# EDP_new_schematic.net
KiCad netlist of a schematic drawn in Altium Designer
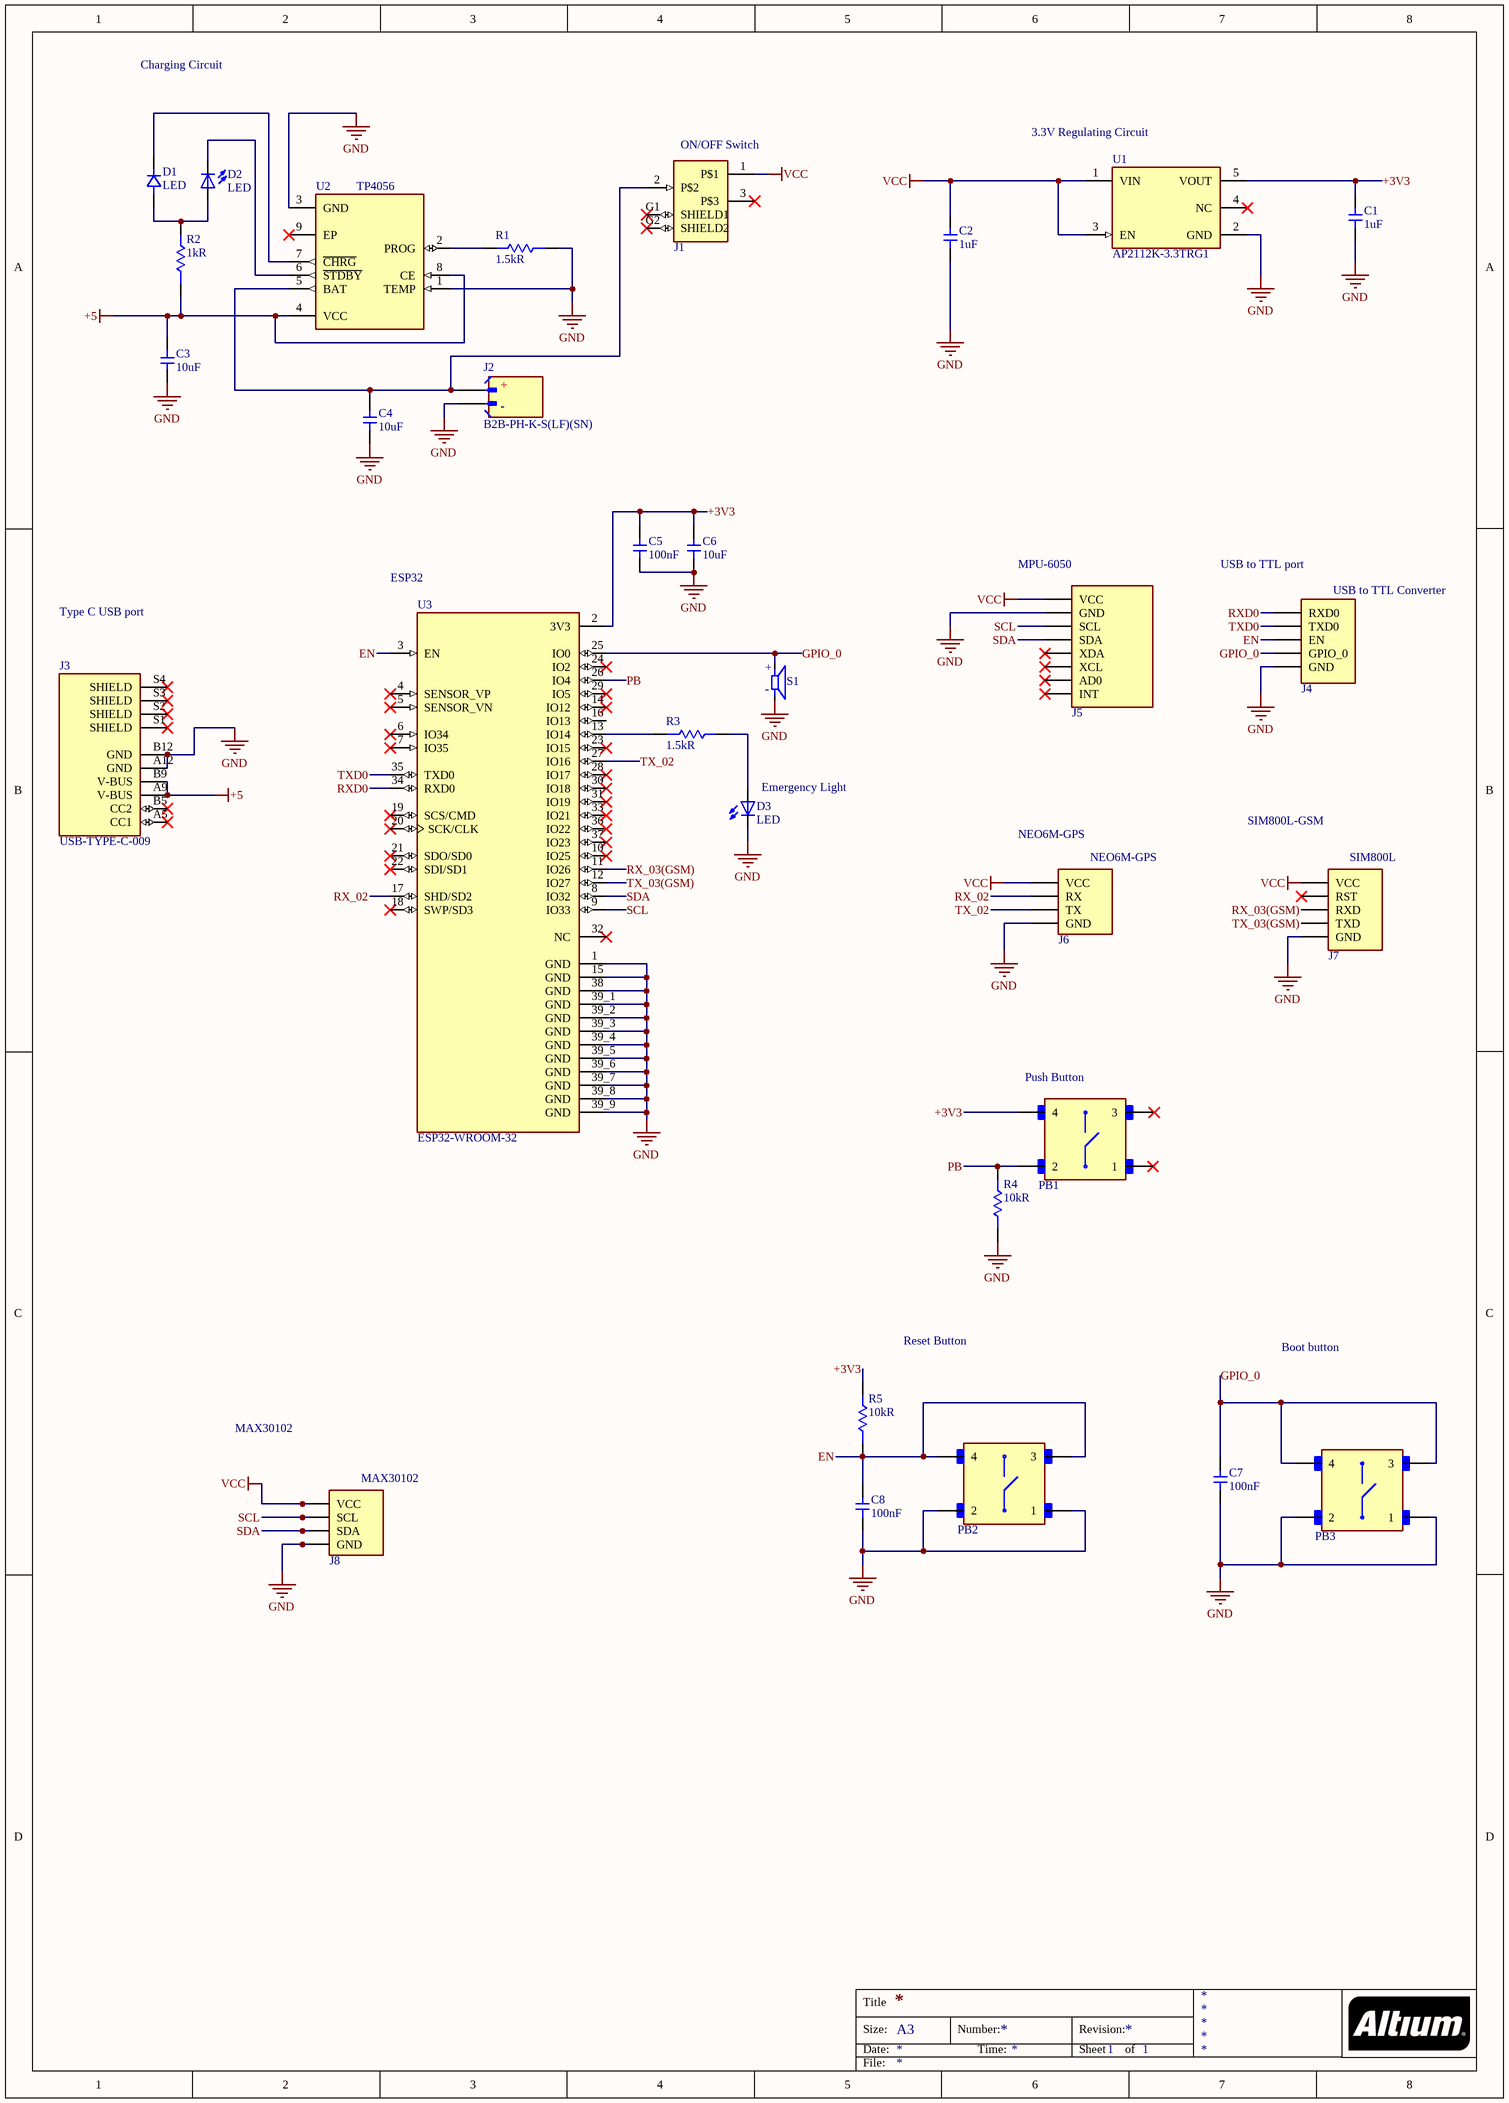
[diagram p0: EDP_new_schematic.SchDoc]

(export (version "E")
  (design (tool "Eeschema 10.0.6"))
  (components
    (comp (ref "C1")
      (value "1uF")
      (footprint "C0805C105K4RACTU")
      (fields
        (field (name "MANUFACTURER") "KEMET")
        (field (name "MANUFACTURER PART NUMBER") "C0805C105K4RACTU")
      )
      (libsource (lib "EDP_integrated_library") (part "C0805C105K4RACTU"))
    )
    (comp (ref "C2")
      (value "1uF")
      (footprint "C0805C105K4RACTU")
      (fields
        (field (name "MANUFACTURER") "KEMET")
        (field (name "MANUFACTURER PART NUMBER") "C0805C105K4RACTU")
      )
      (libsource (lib "EDP_integrated_library") (part "C0805C105K4RACTU"))
    )
    (comp (ref "C3")
      (value "10uF")
      (footprint "C0805C106K3PACTU")
      (fields
        (field (name "MANUFACTURER") "KEMET")
        (field (name "MANUFACTURER PART NUMBER") "C0805C106K3PACTU")
      )
      (libsource (lib "Integrated_Library2") (part "C0805C106K3PACTU"))
    )
    (comp (ref "C4")
      (value "10uF")
      (footprint "C0805C106K3PACTU")
      (fields
        (field (name "MANUFACTURER") "KEMET")
        (field (name "MANUFACTURER PART NUMBER") "C0805C106K3PACTU")
      )
      (libsource (lib "Integrated_Library2") (part "C0805C106K3PACTU"))
    )
    (comp (ref "C5")
      (value "100nF")
      (footprint "C0805C104K5RACTU")
      (fields
        (field (name "MANUFACTURER") "KEMET")
        (field (name "MANUFACTURER PART NUMBER") "C0805C104K5RACTU")
      )
      (libsource (lib "EDP_integrated_library") (part "C0805C104K5RACTU"))
    )
    (comp (ref "C6")
      (value "10uF")
      (footprint "C0805C106K3PACTU")
      (fields
        (field (name "MANUFACTURER") "KEMET")
        (field (name "MANUFACTURER PART NUMBER") "C0805C106K3PACTU")
      )
      (libsource (lib "Integrated_Library2") (part "C0805C106K3PACTU"))
    )
    (comp (ref "C7")
      (value "100nF")
      (footprint "C0805C104K5RACTU")
      (fields
        (field (name "MANUFACTURER") "KEMET")
        (field (name "MANUFACTURER PART NUMBER") "C0805C104K5RACTU")
      )
      (libsource (lib "EDP_integrated_library") (part "C0805C104K5RACTU"))
    )
    (comp (ref "C8")
      (value "100nF")
      (footprint "C0805C104K5RACTU")
      (fields
        (field (name "MANUFACTURER") "KEMET")
        (field (name "MANUFACTURER PART NUMBER") "C0805C104K5RACTU")
      )
      (libsource (lib "EDP_integrated_library") (part "C0805C104K5RACTU"))
    )
    (comp (ref "D1")
      (value "LED")
      (footprint "150080RS75000")
      (description "Single Color LED, Red, Water Clear, 1.4mm")
      (fields
        (field (name "MANUFACTURER") "Wurth Electronics")
        (field (name "MANUFACTURER PART NUMBER") "150080RS75000")
      )
      (libsource (lib "EDP_integrated_library") (part "150080RS75000"))
    )
    (comp (ref "D2")
      (value "LED")
      (footprint "TLLR4400")
      (description "LED; Red; 1.2mcd; 3.2mmDia.; T-1; 7mA; 1.9V; 635nm; +/-25deg; GaAsP on GaP; 15V")
      (fields (field (name "MANUFACTURER") "Vishay") (field (name "MANUFACTURER PART NUMBER") "TLLR4400"))
      (libsource (lib "EDP_integrated_library") (part "TLLR4400"))
    )
    (comp (ref "D3")
      (value "LED")
      (footprint "TLLR4400")
      (description "LED; Red; 1.2mcd; 3.2mmDia.; T-1; 7mA; 1.9V; 635nm; +/-25deg; GaAsP on GaP; 15V")
      (fields (field (name "MANUFACTURER") "Vishay") (field (name "MANUFACTURER PART NUMBER") "TLLR4400"))
      (libsource (lib "EDP_integrated_library") (part "TLLR4400"))
    )
    (comp (ref "J1")
      (value "OS102011MA1QN1")
      (footprint "OS102011MA1QN1_connector")
      (libsource (lib "EDP_integrated_library") (part "OS102011MA1QN1"))
    )
    (comp (ref "J2")
      (value "B2B-PH-K-S (LF)(SN)")
      (footprint "B2B-PH-K-S (LF)(SN)")
      (fields
        (field (name "MANUFACTURER") "JST")
        (field (name "MANUFACTURER PART NUMBER") "B2B-PH-K-S(LF)(SN)")
      )
      (libsource (lib "EDP_integrated_library") (part "B2B-PH-K-S (LF)(SN)"))
    )
    (comp (ref "J3")
      (value "USB-TYPE-C-009")
      (footprint "USB-TYPE-C-009")
      (libsource (lib "EDP_integrated_library") (part "USB-TYPE-C-009"))
    )
    (comp (ref "J4")
      (value "USB-TTL")
      (footprint "USB-TTL")
      (libsource (lib "EDP_integrated_library") (part "USB-TTL"))
    )
    (comp (ref "J5")
      (value "MPU-6050")
      (footprint "MPU-6050")
      (description "Board Stacking Connector, 14 Contact(s), 1 Row(s), Male, Straight, Solder Terminal")
      (fields
        (field (name "MANUFACTURER") "Samtec")
        (field (name "MANUFACTURER PART NUMBER") "MTLW-114-07-T-S-235")
      )
      (libsource (lib "EDP_integrated_library") (part "MPU-6050"))
    )
    (comp (ref "J6")
      (value "NEO6M-GPS")
      (footprint "NEO6M-GPS")
      (libsource (lib "EDP_integrated_library") (part "NEO6M-GPS"))
    )
    (comp (ref "J7")
      (value "SIM800L")
      (footprint "SIM800L")
      (libsource (lib "EDP_integrated_library") (part "SIM800L"))
    )
    (comp (ref "J8")
      (value "MAX30102")
      (footprint "MAX30102_connector")
      (libsource (lib "EDP_integrated_library") (part "MAX30102"))
    )
    (comp (ref "PB1")
      (value "B3F-1000")
      (footprint "SW_B3F-1000")
      (libsource (lib "EDP_integrated_library") (part "B3F-1000"))
    )
    (comp (ref "PB2")
      (value "B3F-1000")
      (footprint "SW_B3F-1000")
      (libsource (lib "EDP_integrated_library") (part "B3F-1000"))
    )
    (comp (ref "PB3")
      (value "B3F-1000")
      (footprint "SW_B3F-1000")
      (libsource (lib "EDP_integrated_library") (part "B3F-1000"))
    )
    (comp (ref "R1")
      (value "1.5kR")
      (footprint "RC0805FR-071K5L")
      (fields
        (field (name "MANUFACTURER") "Yageo")
        (field (name "MANUFACTURER PART NUMBER") "RC0805FR-071K5L")
        (field (name "TOLERANCE") "1%")
      )
      (libsource (lib "EDP_integrated_library") (part "RC0805FR-071K5L"))
    )
    (comp (ref "R2")
      (value "1kR")
      (footprint "RC0805FR-071KL")
      (fields
        (field (name "MANUFACTURER") "Yageo")
        (field (name "MANUFACTURER PART NUMBER") "RC0805FR-071KL")
        (field (name "TOLERANCE") "1%")
      )
      (libsource (lib "EDP_integrated_library") (part "RC0805FR-071KL"))
    )
    (comp (ref "R3")
      (value "1.5kR")
      (footprint "RC0805FR-071K5L")
      (fields
        (field (name "MANUFACTURER") "Yageo")
        (field (name "MANUFACTURER PART NUMBER") "RC0805FR-071K5L")
        (field (name "TOLERANCE") "1%")
      )
      (libsource (lib "EDP_integrated_library") (part "RC0805FR-071K5L"))
    )
    (comp (ref "R4")
      (value "10kR")
      (footprint "RC0805JR-0710KL")
      (fields
        (field (name "MANUFACTURER") "Yageo")
        (field (name "MANUFACTURER PART NUMBER") "RC0805JR-0710KL")
        (field (name "TOLERANCE") "5%")
      )
      (libsource (lib "EDP_integrated_library") (part "RC0805JR-0710KL"))
    )
    (comp (ref "R5")
      (value "10kR")
      (footprint "RC0805JR-0710KL")
      (fields
        (field (name "MANUFACTURER") "Yageo")
        (field (name "MANUFACTURER PART NUMBER") "RC0805JR-0710KL")
        (field (name "TOLERANCE") "5%")
      )
      (libsource (lib "EDP_integrated_library") (part "RC0805JR-0710KL"))
    )
    (comp (ref "S1")
      (value "Speaker")
      (footprint "Speaker")
      (libsource (lib "EDP_integrated_library") (part "Speaker"))
    )
    (comp (ref "U1")
      (value "AP2112K-3.3TRG1")
      (footprint "FP-SOT25-IPC_A")
      (description "IC REG LINEAR 3.3V 600MA SOT25")
      (libsource (lib "Altium Content Vault") (part "c8ab751aee5229183125ab046a11caa"))
    )
    (comp (ref "U2")
      (value "TP4056")
      (footprint "TP4056_chip")
      (libsource (lib "EDP_integrated_library") (part "TP4056_chip"))
    )
    (comp (ref "U3")
      (value "ESP32-WROOM-32")
      (footprint "ESP32-WROOM-32_chip")
      (libsource (lib "EDP_integrated_library") (part "ESP32-WROOM-32"))
    )
  )
  (nets
    (net (code "1") (name "+5") (class "Default")
      (node (ref "C3") (pin "1") (pinfunction "1_1") (pintype "passive"))
      (node (ref "J3") (pin "A9") (pinfunction "V-BUS_A9") (pintype "power_in"))
      (node (ref "J3") (pin "B9") (pinfunction "V-BUS_B9") (pintype "power_in"))
      (node (ref "R2") (pin "1") (pinfunction "1_1") (pintype "passive"))
      (node (ref "U2") (pin "4") (pinfunction "VCC_4") (pintype "power_in"))
      (node (ref "U2") (pin "8") (pinfunction "CE_8") (pintype "input"))
    )
    (net (code "2") (name "/+3V3") (class "Default")
      (node (ref "C1") (pin "2") (pinfunction "2_2") (pintype "passive"))
      (node (ref "C5") (pin "2") (pinfunction "2_2") (pintype "passive"))
      (node (ref "C6") (pin "2") (pinfunction "2_2") (pintype "passive"))
      (node (ref "PB1") (pin "4") (pinfunction "4_4") (pintype "passive"))
      (node (ref "R5") (pin "2") (pinfunction "2_2") (pintype "passive"))
      (node (ref "U1") (pin "5") (pinfunction "VOUT_5") (pintype "power_in"))
      (node (ref "U3") (pin "2") (pinfunction "3V3_2") (pintype "power_in"))
    )
    (net (code "3") (name "/EN") (class "Default")
      (node (ref "C8") (pin "2") (pinfunction "2_2") (pintype "passive"))
      (node (ref "J4") (pin "03") (pinfunction "EN_03") (pintype "passive"))
      (node (ref "PB2") (pin "3") (pinfunction "3_3") (pintype "passive"))
      (node (ref "PB2") (pin "4") (pinfunction "4_4") (pintype "passive"))
      (node (ref "R5") (pin "1") (pinfunction "1_1") (pintype "passive"))
      (node (ref "U3") (pin "3") (pinfunction "EN_3") (pintype "input"))
    )
    (net (code "4") (name "/GPIO_0") (class "Default")
      (node (ref "C7") (pin "2") (pinfunction "2_2") (pintype "passive"))
      (node (ref "J4") (pin "04") (pinfunction "GPIO_0_04") (pintype "passive"))
      (node (ref "PB3") (pin "3") (pinfunction "3_3") (pintype "passive"))
      (node (ref "PB3") (pin "4") (pinfunction "4_4") (pintype "passive"))
      (node (ref "S1") (pin "P") (pinfunction "0_P") (pintype "passive"))
      (node (ref "U3") (pin "25") (pinfunction "IO0_25") (pintype "bidirectional"))
    )
    (net (code "5") (name "/PB") (class "Default")
      (node (ref "PB1") (pin "2") (pinfunction "2_2") (pintype "passive"))
      (node (ref "R4") (pin "2") (pinfunction "2_2") (pintype "passive"))
      (node (ref "U3") (pin "26") (pinfunction "IO4_26") (pintype "bidirectional"))
    )
    (net (code "6") (name "/RXD0") (class "Default")
      (node (ref "J4") (pin "01") (pinfunction "RXD0_01") (pintype "passive"))
      (node (ref "U3") (pin "34") (pinfunction "RXD0_34") (pintype "bidirectional"))
    )
    (net (code "7") (name "/RX_02") (class "Default")
      (node (ref "J6") (pin "02") (pinfunction "RX_02") (pintype "passive"))
      (node (ref "U3") (pin "17") (pinfunction "SHD/SD2_17") (pintype "bidirectional"))
    )
    (net (code "8") (name "/RX_03(GSM)") (class "Default")
      (node (ref "J7") (pin "03") (pinfunction "RXD_03") (pintype "passive"))
      (node (ref "U3") (pin "11") (pinfunction "IO26_11") (pintype "bidirectional"))
    )
    (net (code "9") (name "/SCL") (class "Default")
      (node (ref "J5") (pin "03") (pinfunction "SCL_03") (pintype "passive"))
      (node (ref "J8") (pin "02") (pinfunction "SCL_02") (pintype "passive"))
      (node (ref "U3") (pin "9") (pinfunction "IO33_9") (pintype "bidirectional"))
    )
    (net (code "10") (name "/SDA") (class "Default")
      (node (ref "J5") (pin "04") (pinfunction "SDA_04") (pintype "passive"))
      (node (ref "J8") (pin "03") (pinfunction "SDA_03") (pintype "passive"))
      (node (ref "U3") (pin "8") (pinfunction "IO32_8") (pintype "bidirectional"))
    )
    (net (code "11") (name "/TXD0") (class "Default")
      (node (ref "J4") (pin "02") (pinfunction "TXD0_02") (pintype "passive"))
      (node (ref "U3") (pin "35") (pinfunction "TXD0_35") (pintype "bidirectional"))
    )
    (net (code "12") (name "/TX_02") (class "Default")
      (node (ref "J6") (pin "03") (pinfunction "TX_03") (pintype "passive"))
      (node (ref "U3") (pin "27") (pinfunction "IO16_27") (pintype "bidirectional"))
    )
    (net (code "13") (name "/TX_03(GSM)") (class "Default")
      (node (ref "J7") (pin "04") (pinfunction "TXD_04") (pintype "passive"))
      (node (ref "U3") (pin "12") (pinfunction "IO27_12") (pintype "bidirectional"))
    )
    (net (code "14") (name "GND") (class "Default")
      (node (ref "C1") (pin "1") (pinfunction "1_1") (pintype "passive"))
      (node (ref "C2") (pin "1") (pinfunction "1_1") (pintype "passive"))
      (node (ref "C3") (pin "2") (pinfunction "2_2") (pintype "passive"))
      (node (ref "C4") (pin "1") (pinfunction "1_1") (pintype "passive"))
      (node (ref "C5") (pin "1") (pinfunction "1_1") (pintype "passive"))
      (node (ref "C6") (pin "1") (pinfunction "1_1") (pintype "passive"))
      (node (ref "C7") (pin "1") (pinfunction "1_1") (pintype "passive"))
      (node (ref "C8") (pin "1") (pinfunction "1_1") (pintype "passive"))
      (node (ref "D3") (pin "K") (pinfunction "C_K") (pintype "passive"))
      (node (ref "J2") (pin "2") (pinfunction "2_2") (pintype "passive"))
      (node (ref "J3") (pin "A12") (pinfunction "GND_A12") (pintype "power_in"))
      (node (ref "J3") (pin "B12") (pinfunction "GND_B12") (pintype "power_in"))
      (node (ref "J4") (pin "05") (pinfunction "GND_05") (pintype "passive"))
      (node (ref "J5") (pin "02") (pinfunction "GND_02") (pintype "passive"))
      (node (ref "J6") (pin "04") (pinfunction "GND_04") (pintype "passive"))
      (node (ref "J7") (pin "05") (pinfunction "GND_05") (pintype "passive"))
      (node (ref "J8") (pin "04") (pinfunction "GND_04") (pintype "passive"))
      (node (ref "PB2") (pin "1") (pinfunction "1_1") (pintype "passive"))
      (node (ref "PB2") (pin "2") (pinfunction "2_2") (pintype "passive"))
      (node (ref "PB3") (pin "1") (pinfunction "1_1") (pintype "passive"))
      (node (ref "PB3") (pin "2") (pinfunction "2_2") (pintype "passive"))
      (node (ref "R1") (pin "1") (pinfunction "1_1") (pintype "passive"))
      (node (ref "R4") (pin "1") (pinfunction "1_1") (pintype "passive"))
      (node (ref "S1") (pin "N") (pintype "passive"))
      (node (ref "U1") (pin "2") (pinfunction "GND_2") (pintype "power_in"))
      (node (ref "U2") (pin "1") (pinfunction "TEMP_1") (pintype "input"))
      (node (ref "U2") (pin "3") (pinfunction "GND_3") (pintype "power_in"))
      (node (ref "U3") (pin "1") (pinfunction "GND_1") (pintype "power_in"))
      (node (ref "U3") (pin "15") (pinfunction "GND_15") (pintype "power_in"))
      (node (ref "U3") (pin "38") (pinfunction "GND_38") (pintype "power_in"))
      (node (ref "U3") (pin "39_1") (pinfunction "GND_39_1") (pintype "power_in"))
      (node (ref "U3") (pin "39_2") (pinfunction "GND_39_2") (pintype "power_in"))
      (node (ref "U3") (pin "39_3") (pinfunction "GND_39_3") (pintype "power_in"))
      (node (ref "U3") (pin "39_4") (pinfunction "GND_39_4") (pintype "power_in"))
      (node (ref "U3") (pin "39_5") (pinfunction "GND_39_5") (pintype "power_in"))
      (node (ref "U3") (pin "39_6") (pinfunction "GND_39_6") (pintype "power_in"))
      (node (ref "U3") (pin "39_7") (pinfunction "GND_39_7") (pintype "power_in"))
      (node (ref "U3") (pin "39_8") (pinfunction "GND_39_8") (pintype "power_in"))
      (node (ref "U3") (pin "39_9") (pinfunction "GND_39_9") (pintype "power_in"))
    )
    (net (code "15") (name "Net-(D1-Pad1)") (class "Default")
      (node (ref "D1") (pin "1") (pinfunction "1_1") (pintype "passive"))
      (node (ref "D2") (pin "A") (pinfunction "A_A") (pintype "passive"))
      (node (ref "R2") (pin "2") (pinfunction "2_2") (pintype "passive"))
    )
    (net (code "16") (name "Net-(D2-C)") (class "Default")
      (node (ref "D2") (pin "K") (pinfunction "C_K") (pintype "passive"))
      (node (ref "U2") (pin "6") (pinfunction "~{STDBY}_6") (pintype "output"))
    )
    (net (code "17") (name "Net-(D3-PadA)") (class "Default")
      (node (ref "D3") (pin "A") (pinfunction "A_A") (pintype "passive"))
      (node (ref "R3") (pin "2") (pinfunction "2_2") (pintype "passive"))
    )
    (net (code "18") (name "Net-(J1-P$2)") (class "Default")
      (node (ref "C4") (pin "2") (pinfunction "2_2") (pintype "passive"))
      (node (ref "J1") (pin "2") (pinfunction "P$2_2") (pintype "input"))
      (node (ref "J2") (pin "1") (pinfunction "1_1") (pintype "passive"))
      (node (ref "U2") (pin "5") (pinfunction "BAT_5") (pintype "output"))
    )
    (net (code "19") (name "Net-(U2-PROG)") (class "Default")
      (node (ref "R1") (pin "2") (pinfunction "2_2") (pintype "passive"))
      (node (ref "U2") (pin "2") (pinfunction "PROG_2") (pintype "bidirectional"))
    )
    (net (code "20") (name "Net-(U2-~{CHRG})") (class "Default")
      (node (ref "D1") (pin "2") (pinfunction "2_2") (pintype "passive"))
      (node (ref "U2") (pin "7") (pinfunction "~{CHRG}_7") (pintype "output"))
    )
    (net (code "21") (name "Net-(U3-IO14)") (class "Default")
      (node (ref "R3") (pin "1") (pinfunction "1_1") (pintype "passive"))
      (node (ref "U3") (pin "13") (pinfunction "IO14_13") (pintype "bidirectional"))
    )
    (net (code "22") (name "VCC") (class "Default")
      (node (ref "C2") (pin "2") (pinfunction "2_2") (pintype "passive"))
      (node (ref "J1") (pin "1") (pinfunction "P$1_1") (pintype "power_in"))
      (node (ref "J5") (pin "01") (pinfunction "VCC_01") (pintype "passive"))
      (node (ref "J6") (pin "01") (pinfunction "VCC_01") (pintype "passive"))
      (node (ref "J7") (pin "01") (pinfunction "VCC_01") (pintype "passive"))
      (node (ref "J8") (pin "01") (pinfunction "VCC_01") (pintype "passive"))
      (node (ref "U1") (pin "1") (pinfunction "VIN_1") (pintype "power_in"))
      (node (ref "U1") (pin "3") (pinfunction "EN_3") (pintype "input"))
    )
    (net (code "23") (name "unconnected-(J1-P$3-Pad3)") (class "Default")
      (node (ref "J1") (pin "3") (pinfunction "P$3_3") (pintype "power_in+no_connect"))
    )
    (net (code "24") (name "unconnected-(J1-SHIELD1-PadG1)") (class "Default")
      (node (ref "J1") (pin "G1") (pinfunction "SHIELD1_G1") (pintype "bidirectional+no_connect"))
    )
    (net (code "25") (name "unconnected-(J1-SHIELD2-PadG2)") (class "Default")
      (node (ref "J1") (pin "G2") (pinfunction "SHIELD2_G2") (pintype "bidirectional+no_connect"))
    )
    (net (code "26") (name "unconnected-(J3-CC1-PadA5)") (class "Default")
      (node (ref "J3") (pin "A5") (pinfunction "CC1_A5") (pintype "bidirectional+no_connect"))
    )
    (net (code "27") (name "unconnected-(J3-CC2-PadB5)") (class "Default")
      (node (ref "J3") (pin "B5") (pinfunction "CC2_B5") (pintype "bidirectional+no_connect"))
    )
    (net (code "28") (name "unconnected-(J3-SHIELD-PadS1)") (class "Default")
      (node (ref "J3") (pin "S1") (pinfunction "SHIELD_S1") (pintype "passive+no_connect"))
    )
    (net (code "29") (name "unconnected-(J3-SHIELD-PadS2)") (class "Default")
      (node (ref "J3") (pin "S2") (pinfunction "SHIELD_S2") (pintype "passive+no_connect"))
    )
    (net (code "30") (name "unconnected-(J3-SHIELD-PadS3)") (class "Default")
      (node (ref "J3") (pin "S3") (pinfunction "SHIELD_S3") (pintype "passive+no_connect"))
    )
    (net (code "31") (name "unconnected-(J3-SHIELD-PadS4)") (class "Default")
      (node (ref "J3") (pin "S4") (pinfunction "SHIELD_S4") (pintype "passive+no_connect"))
    )
    (net (code "32") (name "unconnected-(J5-AD0-Pad07)") (class "Default")
      (node (ref "J5") (pin "07") (pinfunction "AD0_07") (pintype "passive+no_connect"))
    )
    (net (code "33") (name "unconnected-(J5-INT-Pad08)") (class "Default")
      (node (ref "J5") (pin "08") (pinfunction "INT_08") (pintype "passive+no_connect"))
    )
    (net (code "34") (name "unconnected-(J5-XCL-Pad06)") (class "Default")
      (node (ref "J5") (pin "06") (pinfunction "XCL_06") (pintype "passive+no_connect"))
    )
    (net (code "35") (name "unconnected-(J5-XDA-Pad05)") (class "Default")
      (node (ref "J5") (pin "05") (pinfunction "XDA_05") (pintype "passive+no_connect"))
    )
    (net (code "36") (name "unconnected-(J7-RST-Pad02)") (class "Default")
      (node (ref "J7") (pin "02") (pinfunction "RST_02") (pintype "passive+no_connect"))
    )
    (net (code "37") (name "unconnected-(PB1-Pad1)") (class "Default")
      (node (ref "PB1") (pin "1") (pinfunction "1_1") (pintype "passive+no_connect"))
    )
    (net (code "38") (name "unconnected-(PB1-Pad3)") (class "Default")
      (node (ref "PB1") (pin "3") (pinfunction "3_3") (pintype "passive"))
    )
    (net (code "39") (name "unconnected-(U1-NC-Pad4)") (class "Default")
      (node (ref "U1") (pin "4") (pinfunction "NC_4") (pintype "passive+no_connect"))
    )
    (net (code "40") (name "unconnected-(U2-EP-Pad9)") (class "Default")
      (node (ref "U2") (pin "9") (pinfunction "EP_9") (pintype "passive+no_connect"))
    )
    (net (code "41") (name "unconnected-(U3-IO2-Pad24)") (class "Default")
      (node (ref "U3") (pin "24") (pinfunction "IO2_24") (pintype "bidirectional+no_connect"))
    )
    (net (code "42") (name "unconnected-(U3-IO5-Pad29)") (class "Default")
      (node (ref "U3") (pin "29") (pinfunction "IO5_29") (pintype "bidirectional+no_connect"))
    )
    (net (code "43") (name "unconnected-(U3-IO12-Pad14)") (class "Default")
      (node (ref "U3") (pin "14") (pinfunction "IO12_14") (pintype "bidirectional+no_connect"))
    )
    (net (code "44") (name "unconnected-(U3-IO13-Pad16)") (class "Default")
      (node (ref "U3") (pin "16") (pinfunction "IO13_16") (pintype "bidirectional"))
    )
    (net (code "45") (name "unconnected-(U3-IO15-Pad23)") (class "Default")
      (node (ref "U3") (pin "23") (pinfunction "IO15_23") (pintype "bidirectional+no_connect"))
    )
    (net (code "46") (name "unconnected-(U3-IO17-Pad28)") (class "Default")
      (node (ref "U3") (pin "28") (pinfunction "IO17_28") (pintype "bidirectional+no_connect"))
    )
    (net (code "47") (name "unconnected-(U3-IO18-Pad30)") (class "Default")
      (node (ref "U3") (pin "30") (pinfunction "IO18_30") (pintype "bidirectional+no_connect"))
    )
    (net (code "48") (name "unconnected-(U3-IO19-Pad31)") (class "Default")
      (node (ref "U3") (pin "31") (pinfunction "IO19_31") (pintype "bidirectional+no_connect"))
    )
    (net (code "49") (name "unconnected-(U3-IO21-Pad33)") (class "Default")
      (node (ref "U3") (pin "33") (pinfunction "IO21_33") (pintype "bidirectional+no_connect"))
    )
    (net (code "50") (name "unconnected-(U3-IO22-Pad36)") (class "Default")
      (node (ref "U3") (pin "36") (pinfunction "IO22_36") (pintype "bidirectional+no_connect"))
    )
    (net (code "51") (name "unconnected-(U3-IO23-Pad37)") (class "Default")
      (node (ref "U3") (pin "37") (pinfunction "IO23_37") (pintype "bidirectional+no_connect"))
    )
    (net (code "52") (name "unconnected-(U3-IO25-Pad10)") (class "Default")
      (node (ref "U3") (pin "10") (pinfunction "IO25_10") (pintype "bidirectional+no_connect"))
    )
    (net (code "53") (name "unconnected-(U3-IO34-Pad6)") (class "Default")
      (node (ref "U3") (pin "6") (pinfunction "IO34_6") (pintype "input+no_connect"))
    )
    (net (code "54") (name "unconnected-(U3-IO35-Pad7)") (class "Default")
      (node (ref "U3") (pin "7") (pinfunction "IO35_7") (pintype "input+no_connect"))
    )
    (net (code "55") (name "unconnected-(U3-NC-Pad32)") (class "Default")
      (node (ref "U3") (pin "32") (pinfunction "NC_32") (pintype "passive+no_connect"))
    )
    (net (code "56") (name "unconnected-(U3-SCK{slash}CLK-Pad20)") (class "Default")
      (node (ref "U3") (pin "20") (pinfunction "SCK/CLK_20") (pintype "bidirectional+no_connect"))
    )
    (net (code "57") (name "unconnected-(U3-SCS{slash}CMD-Pad19)") (class "Default")
      (node (ref "U3") (pin "19") (pinfunction "SCS/CMD_19") (pintype "bidirectional+no_connect"))
    )
    (net (code "58") (name "unconnected-(U3-SDI{slash}SD1-Pad22)") (class "Default")
      (node (ref "U3") (pin "22") (pinfunction "SDI/SD1_22") (pintype "bidirectional+no_connect"))
    )
    (net (code "59") (name "unconnected-(U3-SDO{slash}SD0-Pad21)") (class "Default")
      (node (ref "U3") (pin "21") (pinfunction "SDO/SD0_21") (pintype "bidirectional+no_connect"))
    )
    (net (code "60") (name "unconnected-(U3-SENSOR_VN-Pad5)") (class "Default")
      (node (ref "U3") (pin "5") (pinfunction "SENSOR_VN_5") (pintype "input+no_connect"))
    )
    (net (code "61") (name "unconnected-(U3-SENSOR_VP-Pad4)") (class "Default")
      (node (ref "U3") (pin "4") (pinfunction "SENSOR_VP_4") (pintype "input+no_connect"))
    )
    (net (code "62") (name "unconnected-(U3-SWP{slash}SD3-Pad18)") (class "Default")
      (node (ref "U3") (pin "18") (pinfunction "SWP/SD3_18") (pintype "bidirectional+no_connect"))
    )
  )
)
